# stm32.net
KiCad netlist of a schematic drawn in Altium Designer
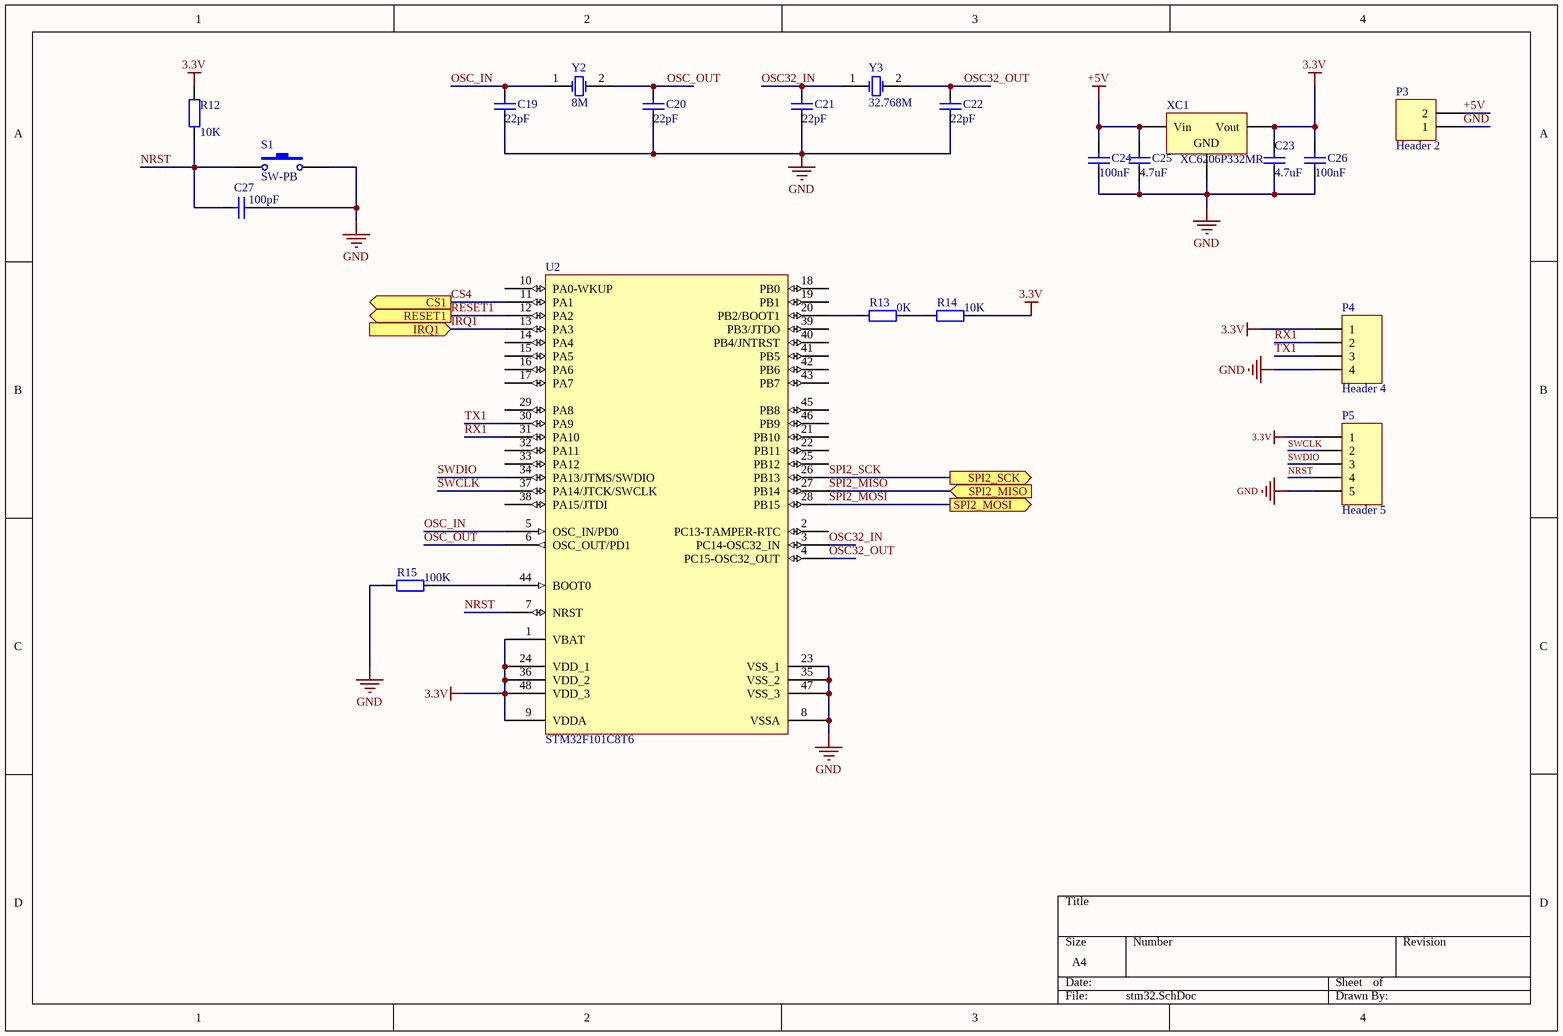
[diagram p0: stm32.SchDoc]

(export (version "E")
  (design (tool "Eeschema 10.0.6"))
  (components
    (comp (ref "C19")
      (value "22pF")
      (footprint "1608[0603]")
      (description "Capacitor (Semiconductor SIM Model)")
      (fields (field (name "Comment") "Cap Semi") (field (name "PUBLISHER") "Altium Limited"))
      (libsource (lib "Miscellaneous Devices") (part "Cap Semi"))
    )
    (comp (ref "C20")
      (value "22pF")
      (footprint "1608[0603]")
      (description "Capacitor (Semiconductor SIM Model)")
      (fields (field (name "Comment") "Cap Semi") (field (name "PUBLISHER") "Altium Limited"))
      (libsource (lib "Miscellaneous Devices") (part "Cap Semi"))
    )
    (comp (ref "C21")
      (value "22pF")
      (footprint "1608[0603]")
      (description "Capacitor (Semiconductor SIM Model)")
      (fields (field (name "Comment") "Cap Semi") (field (name "PUBLISHER") "Altium Limited"))
      (libsource (lib "Miscellaneous Devices") (part "Cap Semi"))
    )
    (comp (ref "C22")
      (value "22pF")
      (footprint "1608[0603]")
      (description "Capacitor (Semiconductor SIM Model)")
      (fields (field (name "Comment") "Cap Semi") (field (name "PUBLISHER") "Altium Limited"))
      (libsource (lib "Miscellaneous Devices") (part "Cap Semi"))
    )
    (comp (ref "C23")
      (value "4.7uF")
      (footprint "1608[0603]")
      (description "Capacitor (Semiconductor SIM Model)")
      (fields (field (name "Comment") "Cap Semi") (field (name "PUBLISHER") "Altium Limited"))
      (libsource (lib "Miscellaneous Devices") (part "Cap Semi"))
    )
    (comp (ref "C24")
      (value "100nF")
      (footprint "1608[0603]")
      (description "Capacitor (Semiconductor SIM Model)")
      (fields (field (name "Comment") "Cap Semi") (field (name "PUBLISHER") "Altium Limited"))
      (libsource (lib "Miscellaneous Devices") (part "Cap Semi"))
    )
    (comp (ref "C25")
      (value "4.7uF")
      (footprint "1608[0603]")
      (description "Capacitor (Semiconductor SIM Model)")
      (fields (field (name "Comment") "Cap Semi") (field (name "PUBLISHER") "Altium Limited"))
      (libsource (lib "Miscellaneous Devices") (part "Cap Semi"))
    )
    (comp (ref "C26")
      (value "100nF")
      (footprint "1608[0603]")
      (description "Capacitor (Semiconductor SIM Model)")
      (fields (field (name "Comment") "Cap Semi") (field (name "PUBLISHER") "Altium Limited"))
      (libsource (lib "Miscellaneous Devices") (part "Cap Semi"))
    )
    (comp (ref "C27")
      (value "100pF")
      (footprint "1608[0603]")
      (description "Capacitor (Semiconductor SIM Model)")
      (fields (field (name "Comment") "Cap Semi") (field (name "PUBLISHER") "Altium Limited"))
      (libsource (lib "Miscellaneous Devices") (part "Cap Semi"))
    )
    (comp (ref "P3")
      (value "Header 2")
      (footprint "HDR1X2")
      (description "Header, 2-Pin")
      (fields (field (name "PUBLISHER") "Altium Limited"))
      (libsource (lib "Miscellaneous Connectors") (part "Header 2"))
    )
    (comp (ref "P4")
      (value "Header 4")
      (footprint "HDR1X4")
      (description "Header, 4-Pin")
      (fields (field (name "PUBLISHER") "Altium Limited"))
      (libsource (lib "Miscellaneous Connectors") (part "Header 4"))
    )
    (comp (ref "P5")
      (value "Header 5")
      (footprint "HDR1X5")
      (description "Header, 5-Pin")
      (fields (field (name "PUBLISHER") "Altium Limited"))
      (libsource (lib "Miscellaneous Connectors") (part "Header 5"))
    )
    (comp (ref "R12")
      (value "10K")
      (footprint "1608[0603]")
      (description "Resistor")
      (fields (field (name "Comment") "Res2") (field (name "PUBLISHER") "Altium Limited"))
      (libsource (lib "Miscellaneous Devices") (part "Res2"))
    )
    (comp (ref "R13")
      (value "0K")
      (footprint "1608[0603]")
      (description "Resistor")
      (fields (field (name "Comment") "Res2") (field (name "PUBLISHER") "Altium Limited"))
      (libsource (lib "") (part "Res2_1"))
    )
    (comp (ref "R14")
      (value "10K")
      (footprint "1608[0603]")
      (description "Resistor")
      (fields (field (name "Comment") "Res2") (field (name "PUBLISHER") "Altium Limited"))
      (libsource (lib "") (part "Res2_1"))
    )
    (comp (ref "R15")
      (value "100K")
      (footprint "AXIAL-0.4")
      (description "Resistor")
      (fields (field (name "Comment") "Res2") (field (name "PUBLISHER") "Altium Limited"))
      (libsource (lib "") (part "Res2_1"))
    )
    (comp (ref "S1")
      (value "SW-PB")
      (footprint "SPST-2")
      (description "Switch")
      (fields (field (name "PUBLISHER") "Altium Limited"))
      (libsource (lib "Miscellaneous Devices") (part "SW-PB"))
    )
    (comp (ref "U2")
      (value "STM32F101C8T6")
      (footprint "LQFP48_N")
      (description "STM32 ARM-based 32-bit MCU with 64 Kbytes Flash, 48-pin LQFP, Industrial Temperature")
      (fields (field (name "PUBLISHER") "Altium Limited"))
      (libsource (lib "ST Microcontroller 32-Bit STM32") (part "STM32F101C8T6"))
    )
    (comp (ref "XC1")
      (value "XC6206P332MR")
      (footprint "SOT89L")
      (description "Voltage Regulator")
      (fields (field (name "PUBLISHER") "Altium Limited"))
      (libsource (lib "Miscellaneous Devices") (part "Volt Reg"))
    )
    (comp (ref "Y2")
      (value "8M")
      (footprint "HC-48SMD")
      (description "Crystal Oscillator")
      (fields (field (name "PUBLISHER") "Altium Limited"))
      (libsource (lib "Miscellaneous Devices") (part "XTAL"))
    )
    (comp (ref "Y3")
      (value "32.768M")
      (footprint "FC135")
      (description "Crystal Oscillator")
      (fields (field (name "PUBLISHER") "Altium Limited"))
      (libsource (lib "Miscellaneous Devices") (part "XTAL"))
    )
  )
  (nets
    (net (code "1") (name "+5V") (class "Default")
      (node (ref "C24") (pin "2") (pinfunction "2_2") (pintype "passive"))
      (node (ref "C25") (pin "2") (pinfunction "2_2") (pintype "passive"))
      (node (ref "P3") (pin "2") (pinfunction "2_2") (pintype "passive"))
      (node (ref "XC1") (pin "1") (pinfunction "Vin_1") (pintype "passive"))
    )
    (net (code "2") (name "/CS4") (class "Default")
      (node (ref "U2") (pin "11") (pinfunction "PA1_11") (pintype "bidirectional"))
    )
    (net (code "3") (name "/IRQ1") (class "Default")
      (node (ref "U2") (pin "13") (pinfunction "PA3_13") (pintype "bidirectional"))
    )
    (net (code "4") (name "/NRST") (class "Default")
      (node (ref "C27") (pin "1") (pinfunction "1_1") (pintype "passive"))
      (node (ref "P5") (pin "4") (pinfunction "4_4") (pintype "passive"))
      (node (ref "R12") (pin "2") (pinfunction "2_2") (pintype "passive"))
      (node (ref "S1") (pin "1") (pinfunction "1_1") (pintype "passive"))
      (node (ref "U2") (pin "7") (pinfunction "NRST_7") (pintype "bidirectional"))
    )
    (net (code "5") (name "/OSC32_IN") (class "Default")
      (node (ref "C21") (pin "2") (pinfunction "2_2") (pintype "passive"))
      (node (ref "U2") (pin "3") (pinfunction "PC14-OSC32_IN_3") (pintype "bidirectional"))
      (node (ref "Y3") (pin "1") (pinfunction "OSC1_1") (pintype "passive"))
    )
    (net (code "6") (name "/OSC32_OUT") (class "Default")
      (node (ref "C22") (pin "2") (pinfunction "2_2") (pintype "passive"))
      (node (ref "U2") (pin "4") (pinfunction "PC15-OSC32_OUT_4") (pintype "bidirectional"))
      (node (ref "Y3") (pin "2") (pinfunction "OSC2_2") (pintype "passive"))
    )
    (net (code "7") (name "/OSC_IN") (class "Default")
      (node (ref "C19") (pin "2") (pinfunction "2_2") (pintype "passive"))
      (node (ref "U2") (pin "5") (pinfunction "OSC_IN/PD0_5") (pintype "input"))
      (node (ref "Y2") (pin "1") (pinfunction "OSC1_1") (pintype "passive"))
    )
    (net (code "8") (name "/OSC_OUT") (class "Default")
      (node (ref "C20") (pin "2") (pinfunction "2_2") (pintype "passive"))
      (node (ref "U2") (pin "6") (pinfunction "OSC_OUT/PD1_6") (pintype "output"))
      (node (ref "Y2") (pin "2") (pinfunction "OSC2_2") (pintype "passive"))
    )
    (net (code "9") (name "/RESET1") (class "Default")
      (node (ref "U2") (pin "12") (pinfunction "PA2_12") (pintype "bidirectional"))
    )
    (net (code "10") (name "/RX1") (class "Default")
      (node (ref "P4") (pin "2") (pinfunction "2_2") (pintype "passive"))
      (node (ref "U2") (pin "31") (pinfunction "PA10_31") (pintype "bidirectional"))
    )
    (net (code "11") (name "/SPI2_MISO") (class "Default")
      (node (ref "U2") (pin "27") (pinfunction "PB14_27") (pintype "bidirectional"))
    )
    (net (code "12") (name "/SPI2_MOSI") (class "Default")
      (node (ref "U2") (pin "28") (pinfunction "PB15_28") (pintype "bidirectional"))
    )
    (net (code "13") (name "/SPI2_SCK") (class "Default")
      (node (ref "U2") (pin "26") (pinfunction "PB13_26") (pintype "bidirectional"))
    )
    (net (code "14") (name "/SWCLK") (class "Default")
      (node (ref "P5") (pin "2") (pinfunction "2_2") (pintype "passive"))
      (node (ref "U2") (pin "37") (pinfunction "PA14/JTCK/SWCLK_37") (pintype "bidirectional"))
    )
    (net (code "15") (name "/SWDIO") (class "Default")
      (node (ref "P5") (pin "3") (pinfunction "3_3") (pintype "passive"))
      (node (ref "U2") (pin "34") (pinfunction "PA13/JTMS/SWDIO_34") (pintype "bidirectional"))
    )
    (net (code "16") (name "/TX1") (class "Default")
      (node (ref "P4") (pin "3") (pinfunction "3_3") (pintype "passive"))
      (node (ref "U2") (pin "30") (pinfunction "PA9_30") (pintype "bidirectional"))
    )
    (net (code "17") (name "3.3V") (class "Default")
      (node (ref "C23") (pin "2") (pinfunction "2_2") (pintype "passive"))
      (node (ref "C26") (pin "2") (pinfunction "2_2") (pintype "passive"))
      (node (ref "P4") (pin "1") (pinfunction "1_1") (pintype "passive"))
      (node (ref "P5") (pin "1") (pinfunction "1_1") (pintype "passive"))
      (node (ref "R12") (pin "1") (pinfunction "1_1") (pintype "passive"))
      (node (ref "R14") (pin "2") (pinfunction "2_2") (pintype "passive"))
      (node (ref "U2") (pin "1") (pinfunction "VBAT_1") (pintype "power_in"))
      (node (ref "U2") (pin "24") (pinfunction "VDD_1_24") (pintype "power_in"))
      (node (ref "U2") (pin "36") (pinfunction "VDD_2_36") (pintype "power_in"))
      (node (ref "U2") (pin "48") (pinfunction "VDD_3_48") (pintype "power_in"))
      (node (ref "U2") (pin "9") (pinfunction "VDDA_9") (pintype "power_in"))
      (node (ref "XC1") (pin "3") (pinfunction "Vout_3") (pintype "passive"))
    )
    (net (code "18") (name "GND") (class "Default")
      (node (ref "C19") (pin "1") (pinfunction "1_1") (pintype "passive"))
      (node (ref "C20") (pin "1") (pinfunction "1_1") (pintype "passive"))
      (node (ref "C21") (pin "1") (pinfunction "1_1") (pintype "passive"))
      (node (ref "C22") (pin "1") (pinfunction "1_1") (pintype "passive"))
      (node (ref "C23") (pin "1") (pinfunction "1_1") (pintype "passive"))
      (node (ref "C24") (pin "1") (pinfunction "1_1") (pintype "passive"))
      (node (ref "C25") (pin "1") (pinfunction "1_1") (pintype "passive"))
      (node (ref "C26") (pin "1") (pinfunction "1_1") (pintype "passive"))
      (node (ref "C27") (pin "2") (pinfunction "2_2") (pintype "passive"))
      (node (ref "P3") (pin "1") (pinfunction "1_1") (pintype "passive"))
      (node (ref "P4") (pin "4") (pinfunction "4_4") (pintype "passive"))
      (node (ref "P5") (pin "5") (pinfunction "5_5") (pintype "passive"))
      (node (ref "R15") (pin "1") (pinfunction "1_1") (pintype "passive"))
      (node (ref "S1") (pin "2") (pinfunction "2_2") (pintype "passive"))
      (node (ref "U2") (pin "23") (pinfunction "VSS_1_23") (pintype "power_in"))
      (node (ref "U2") (pin "35") (pinfunction "VSS_2_35") (pintype "power_in"))
      (node (ref "U2") (pin "47") (pinfunction "VSS_3_47") (pintype "power_in"))
      (node (ref "U2") (pin "8") (pinfunction "VSSA_8") (pintype "power_in"))
      (node (ref "XC1") (pin "2") (pinfunction "GND_2") (pintype "passive"))
    )
    (net (code "19") (name "Net-(R13-Pad2)") (class "Default")
      (node (ref "R13") (pin "2") (pinfunction "2_2") (pintype "passive"))
      (node (ref "R14") (pin "1") (pinfunction "1_1") (pintype "passive"))
    )
    (net (code "20") (name "Net-(U2-BOOT0)") (class "Default")
      (node (ref "R15") (pin "2") (pinfunction "2_2") (pintype "passive"))
      (node (ref "U2") (pin "44") (pinfunction "BOOT0_44") (pintype "input"))
    )
    (net (code "21") (name "Net-(U2-PB2{slash}BOOT1)") (class "Default")
      (node (ref "R13") (pin "1") (pinfunction "1_1") (pintype "passive"))
      (node (ref "U2") (pin "20") (pinfunction "PB2/BOOT1_20") (pintype "bidirectional"))
    )
    (net (code "22") (name "unconnected-(U2-PA0-WKUP-Pad10)") (class "Default")
      (node (ref "U2") (pin "10") (pinfunction "PA0-WKUP_10") (pintype "bidirectional"))
    )
    (net (code "23") (name "unconnected-(U2-PA4-Pad14)") (class "Default")
      (node (ref "U2") (pin "14") (pinfunction "PA4_14") (pintype "bidirectional"))
    )
    (net (code "24") (name "unconnected-(U2-PA5-Pad15)") (class "Default")
      (node (ref "U2") (pin "15") (pinfunction "PA5_15") (pintype "bidirectional"))
    )
    (net (code "25") (name "unconnected-(U2-PA6-Pad16)") (class "Default")
      (node (ref "U2") (pin "16") (pinfunction "PA6_16") (pintype "bidirectional"))
    )
    (net (code "26") (name "unconnected-(U2-PA7-Pad17)") (class "Default")
      (node (ref "U2") (pin "17") (pinfunction "PA7_17") (pintype "bidirectional"))
    )
    (net (code "27") (name "unconnected-(U2-PA8-Pad29)") (class "Default")
      (node (ref "U2") (pin "29") (pinfunction "PA8_29") (pintype "bidirectional"))
    )
    (net (code "28") (name "unconnected-(U2-PA11-Pad32)") (class "Default")
      (node (ref "U2") (pin "32") (pinfunction "PA11_32") (pintype "bidirectional"))
    )
    (net (code "29") (name "unconnected-(U2-PA12-Pad33)") (class "Default")
      (node (ref "U2") (pin "33") (pinfunction "PA12_33") (pintype "bidirectional"))
    )
    (net (code "30") (name "unconnected-(U2-PA15{slash}JTDI-Pad38)") (class "Default")
      (node (ref "U2") (pin "38") (pinfunction "PA15/JTDI_38") (pintype "bidirectional"))
    )
    (net (code "31") (name "unconnected-(U2-PB0-Pad18)") (class "Default")
      (node (ref "U2") (pin "18") (pinfunction "PB0_18") (pintype "bidirectional"))
    )
    (net (code "32") (name "unconnected-(U2-PB1-Pad19)") (class "Default")
      (node (ref "U2") (pin "19") (pinfunction "PB1_19") (pintype "bidirectional"))
    )
    (net (code "33") (name "unconnected-(U2-PB3{slash}JTDO-Pad39)") (class "Default")
      (node (ref "U2") (pin "39") (pinfunction "PB3/JTDO_39") (pintype "bidirectional"))
    )
    (net (code "34") (name "unconnected-(U2-PB4{slash}JNTRST-Pad40)") (class "Default")
      (node (ref "U2") (pin "40") (pinfunction "PB4/JNTRST_40") (pintype "bidirectional"))
    )
    (net (code "35") (name "unconnected-(U2-PB5-Pad41)") (class "Default")
      (node (ref "U2") (pin "41") (pinfunction "PB5_41") (pintype "bidirectional"))
    )
    (net (code "36") (name "unconnected-(U2-PB6-Pad42)") (class "Default")
      (node (ref "U2") (pin "42") (pinfunction "PB6_42") (pintype "bidirectional"))
    )
    (net (code "37") (name "unconnected-(U2-PB7-Pad43)") (class "Default")
      (node (ref "U2") (pin "43") (pinfunction "PB7_43") (pintype "bidirectional"))
    )
    (net (code "38") (name "unconnected-(U2-PB8-Pad45)") (class "Default")
      (node (ref "U2") (pin "45") (pinfunction "PB8_45") (pintype "bidirectional"))
    )
    (net (code "39") (name "unconnected-(U2-PB9-Pad46)") (class "Default")
      (node (ref "U2") (pin "46") (pinfunction "PB9_46") (pintype "bidirectional"))
    )
    (net (code "40") (name "unconnected-(U2-PB10-Pad21)") (class "Default")
      (node (ref "U2") (pin "21") (pinfunction "PB10_21") (pintype "bidirectional"))
    )
    (net (code "41") (name "unconnected-(U2-PB11-Pad22)") (class "Default")
      (node (ref "U2") (pin "22") (pinfunction "PB11_22") (pintype "bidirectional"))
    )
    (net (code "42") (name "unconnected-(U2-PB12-Pad25)") (class "Default")
      (node (ref "U2") (pin "25") (pinfunction "PB12_25") (pintype "bidirectional"))
    )
    (net (code "43") (name "unconnected-(U2-PC13-TAMPER-RTC-Pad2)") (class "Default")
      (node (ref "U2") (pin "2") (pinfunction "PC13-TAMPER-RTC_2") (pintype "bidirectional"))
    )
  )
)
